# simCon.net
KiCad netlist of a schematic drawn in EAGLE
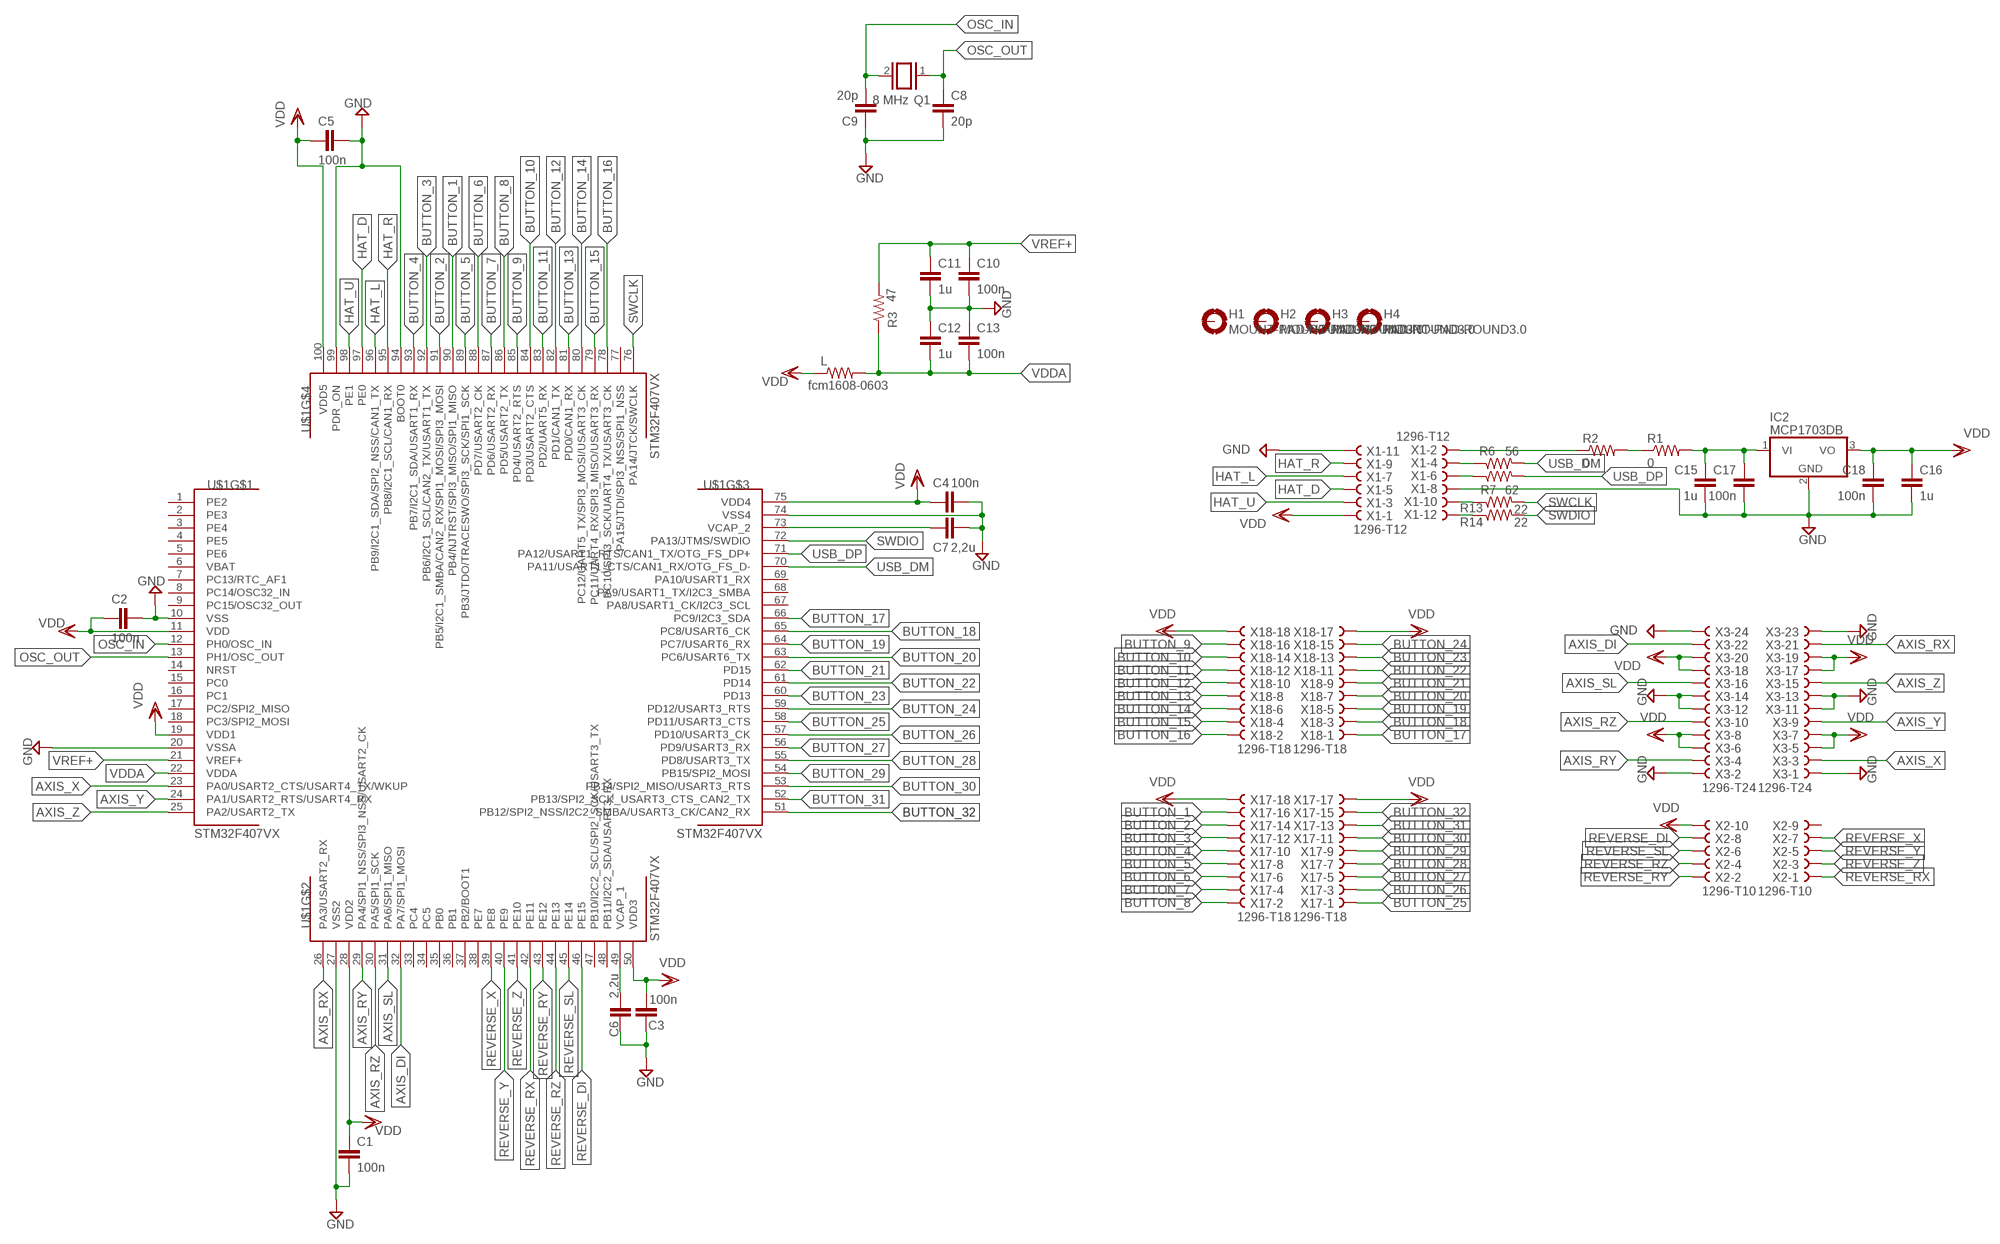
[diagram p0: schematic, sheet 1]

(export (version "E")
  (design (tool "Eeschema 10.0.6"))
  (components
    (comp (ref "C1")
      (value "100n")
      (footprint "eagle-import:C0805K")
      (libsource (lib "eagle-import") (part "C-EUC0805K"))
    )
    (comp (ref "C2")
      (value "100n")
      (footprint "eagle-import:C0805K")
      (libsource (lib "eagle-import") (part "C-EUC0805K"))
    )
    (comp (ref "C3")
      (value "100n")
      (footprint "eagle-import:C0805K")
      (libsource (lib "eagle-import") (part "C-EUC0805K"))
    )
    (comp (ref "C4")
      (value "100n")
      (footprint "eagle-import:C0805K")
      (libsource (lib "eagle-import") (part "C-EUC0805K"))
    )
    (comp (ref "C5")
      (value "100n")
      (footprint "eagle-import:C0805K")
      (libsource (lib "eagle-import") (part "C-EUC0805K"))
    )
    (comp (ref "C6")
      (value "2,2u")
      (footprint "eagle-import:C0805K")
      (libsource (lib "eagle-import") (part "C-EUC0805K"))
    )
    (comp (ref "C7")
      (value "2,2u")
      (footprint "eagle-import:C0805K")
      (libsource (lib "eagle-import") (part "C-EUC0805K"))
    )
    (comp (ref "C8")
      (value "20p")
      (footprint "eagle-import:C0805K")
      (libsource (lib "eagle-import") (part "C-EUC0805K"))
    )
    (comp (ref "C9")
      (value "20p")
      (footprint "eagle-import:C0805K")
      (libsource (lib "eagle-import") (part "C-EUC0805K"))
    )
    (comp (ref "C10")
      (value "100n")
      (footprint "eagle-import:C0805K")
      (libsource (lib "eagle-import") (part "C-EUC0805K"))
    )
    (comp (ref "C11")
      (value "1u")
      (footprint "eagle-import:C0805K")
      (libsource (lib "eagle-import") (part "C-EUC0805K"))
    )
    (comp (ref "C12")
      (value "1u")
      (footprint "eagle-import:C0805K")
      (libsource (lib "eagle-import") (part "C-EUC0805K"))
    )
    (comp (ref "C13")
      (value "100n")
      (footprint "eagle-import:C0805K")
      (libsource (lib "eagle-import") (part "C-EUC0805K"))
    )
    (comp (ref "C15")
      (value "1u")
      (footprint "eagle-import:C0805K")
      (libsource (lib "eagle-import") (part "C-EUC0805K"))
    )
    (comp (ref "C16")
      (value "1u")
      (footprint "eagle-import:C0805K")
      (libsource (lib "eagle-import") (part "C-EUC0805K"))
    )
    (comp (ref "C17")
      (value "100n")
      (footprint "eagle-import:C0805K")
      (libsource (lib "eagle-import") (part "C-EUC0805K"))
    )
    (comp (ref "C18")
      (value "100n")
      (footprint "eagle-import:C0805K")
      (libsource (lib "eagle-import") (part "C-EUC0805K"))
    )
    (comp (ref "H1")
      (value "MOUNT-PAD-ROUND3.0")
      (footprint "eagle-import:3,0-PAD")
      (libsource (lib "eagle-import") (part "MOUNT-PAD-ROUND3.0"))
    )
    (comp (ref "H2")
      (value "MOUNT-PAD-ROUND3.0")
      (footprint "eagle-import:3,0-PAD")
      (libsource (lib "eagle-import") (part "MOUNT-PAD-ROUND3.0"))
    )
    (comp (ref "H3")
      (value "MOUNT-PAD-ROUND3.0")
      (footprint "eagle-import:3,0-PAD")
      (libsource (lib "eagle-import") (part "MOUNT-PAD-ROUND3.0"))
    )
    (comp (ref "H4")
      (value "MOUNT-PAD-ROUND3.0")
      (footprint "eagle-import:3,0-PAD")
      (libsource (lib "eagle-import") (part "MOUNT-PAD-ROUND3.0"))
    )
    (comp (ref "IC2")
      (value "MCP1703DB")
      (footprint "eagle-import:SOT223")
      (libsource (lib "eagle-import") (part "MCP1703DB"))
    )
    (comp (ref "L")
      (value "fcm1608-0603")
      (footprint "eagle-import:M0805")
      (libsource (lib "eagle-import") (part "R-US_M0805"))
    )
    (comp (ref "Q1")
      (value "8 MHz")
      (footprint "eagle-import:QS")
      (libsource (lib "eagle-import") (part "XTAL/S"))
    )
    (comp (ref "R1")
      (value "0")
      (footprint "eagle-import:R1206")
      (libsource (lib "eagle-import") (part "resistor_R-US_R1206"))
    )
    (comp (ref "R2")
      (value "0")
      (footprint "eagle-import:R1206")
      (libsource (lib "eagle-import") (part "resistor_R-US_R1206"))
    )
    (comp (ref "R3")
      (value "47")
      (footprint "eagle-import:M0805")
      (libsource (lib "eagle-import") (part "R-US_M0805"))
    )
    (comp (ref "R6")
      (value "56")
      (footprint "eagle-import:M0805")
      (libsource (lib "eagle-import") (part "R-US_M0805"))
    )
    (comp (ref "R7")
      (value "62")
      (footprint "eagle-import:M0805")
      (libsource (lib "eagle-import") (part "R-US_M0805"))
    )
    (comp (ref "R13")
      (value "22")
      (footprint "eagle-import:M0805")
      (libsource (lib "eagle-import") (part "R-US_M0805"))
    )
    (comp (ref "R14")
      (value "22")
      (footprint "eagle-import:M0805")
      (libsource (lib "eagle-import") (part "R-US_M0805"))
    )
    (comp (ref "U$1")
      (value "STM32F407VX")
      (footprint "eagle-import:LQFP100")
      (libsource (lib "eagle-import") (part "STM32F407VX"))
    )
    (comp (ref "X1")
      (value "1296-T12")
      (footprint "eagle-import:1296-12")
      (libsource (lib "eagle-import") (part "1296-T12"))
    )
    (comp (ref "X2")
      (value "1296-T10")
      (footprint "eagle-import:1296-10")
      (libsource (lib "eagle-import") (part "1296-T10"))
    )
    (comp (ref "X3")
      (value "1296-T24")
      (footprint "eagle-import:1296-24")
      (libsource (lib "eagle-import") (part "1296-T24"))
    )
    (comp (ref "X17")
      (value "1296-T18")
      (footprint "eagle-import:1296-18")
      (libsource (lib "eagle-import") (part "1296-T18"))
    )
    (comp (ref "X18")
      (value "1296-T18")
      (footprint "eagle-import:1296-18")
      (libsource (lib "eagle-import") (part "1296-T18"))
    )
  )
  (nets
    (net (code "1") (name "AXIS_DI") (class "Default")
      (node (ref "U$1") (pin "32") (pinfunction "PA7/SPI1_MOSI_32") (pintype "bidirectional"))
      (node (ref "X3") (pin "22") (pinfunction "B_22") (pintype "passive"))
    )
    (net (code "2") (name "AXIS_RX") (class "Default")
      (node (ref "U$1") (pin "26") (pinfunction "PA3/USART2_RX_26") (pintype "bidirectional"))
      (node (ref "X3") (pin "21") (pinfunction "B_21") (pintype "passive"))
    )
    (net (code "3") (name "AXIS_RY") (class "Default")
      (node (ref "U$1") (pin "29") (pinfunction "PA4/SPI1_NSS/SPI3_NSS/USART2_CK_29") (pintype "bidirectional"))
      (node (ref "X3") (pin "4") (pinfunction "B_4") (pintype "passive"))
    )
    (net (code "4") (name "AXIS_RZ") (class "Default")
      (node (ref "U$1") (pin "30") (pinfunction "PA5/SPI1_SCK_30") (pintype "bidirectional"))
      (node (ref "X3") (pin "10") (pinfunction "B_10") (pintype "passive"))
    )
    (net (code "5") (name "AXIS_SL") (class "Default")
      (node (ref "U$1") (pin "31") (pinfunction "PA6/SPI1_MISO_31") (pintype "bidirectional"))
      (node (ref "X3") (pin "16") (pinfunction "B_16") (pintype "passive"))
    )
    (net (code "6") (name "AXIS_X") (class "Default")
      (node (ref "U$1") (pin "23") (pinfunction "PA0/USART2_CTS/USART4_TX/WKUP_23") (pintype "bidirectional"))
      (node (ref "X3") (pin "3") (pinfunction "B_3") (pintype "passive"))
    )
    (net (code "7") (name "AXIS_Y") (class "Default")
      (node (ref "U$1") (pin "24") (pinfunction "PA1/USART2_RTS/USART4_RX_24") (pintype "bidirectional"))
      (node (ref "X3") (pin "9") (pinfunction "B_9") (pintype "passive"))
    )
    (net (code "8") (name "AXIS_Z") (class "Default")
      (node (ref "U$1") (pin "25") (pinfunction "PA2/USART2_TX_25") (pintype "bidirectional"))
      (node (ref "X3") (pin "15") (pinfunction "B_15") (pintype "passive"))
    )
    (net (code "9") (name "BUTTON_1") (class "Default")
      (node (ref "U$1") (pin "90") (pinfunction "PB4/NJTRST/SPI3_MISO/SPI1_MISO_90") (pintype "bidirectional"))
      (node (ref "X17") (pin "16") (pinfunction "B_16") (pintype "passive"))
    )
    (net (code "10") (name "BUTTON_2") (class "Default")
      (node (ref "U$1") (pin "91") (pinfunction "PB5/I2C1_SMBA/CAN2_RX/SPI1_MOSI/SPI3_MOSI_91") (pintype "bidirectional"))
      (node (ref "X17") (pin "14") (pinfunction "B_14") (pintype "passive"))
    )
    (net (code "11") (name "BUTTON_3") (class "Default")
      (node (ref "U$1") (pin "92") (pinfunction "PB6/I2C1_SCL/CAN2_TX/USART1_TX_92") (pintype "bidirectional"))
      (node (ref "X17") (pin "12") (pinfunction "B_12") (pintype "passive"))
    )
    (net (code "12") (name "BUTTON_4") (class "Default")
      (node (ref "U$1") (pin "93") (pinfunction "PB7/I2C1_SDA/USART1_RX_93") (pintype "bidirectional"))
      (node (ref "X17") (pin "10") (pinfunction "B_10") (pintype "passive"))
    )
    (net (code "13") (name "BUTTON_5") (class "Default")
      (node (ref "U$1") (pin "89") (pinfunction "PB3/JTDO/TRACESWO/SPI3_SCK/SPI1_SCK_89") (pintype "bidirectional"))
      (node (ref "X17") (pin "8") (pinfunction "B_8") (pintype "passive"))
    )
    (net (code "14") (name "BUTTON_6") (class "Default")
      (node (ref "U$1") (pin "88") (pinfunction "PD7/USART2_CK_88") (pintype "bidirectional"))
      (node (ref "X17") (pin "6") (pinfunction "B_6") (pintype "passive"))
    )
    (net (code "15") (name "BUTTON_7") (class "Default")
      (node (ref "U$1") (pin "87") (pinfunction "PD6/USART2_RX_87") (pintype "bidirectional"))
      (node (ref "X17") (pin "4") (pinfunction "B_4") (pintype "passive"))
    )
    (net (code "16") (name "BUTTON_8") (class "Default")
      (node (ref "U$1") (pin "86") (pinfunction "PD5/USART2_TX_86") (pintype "bidirectional"))
      (node (ref "X17") (pin "2") (pinfunction "B_2") (pintype "passive"))
    )
    (net (code "17") (name "BUTTON_9") (class "Default")
      (node (ref "U$1") (pin "85") (pinfunction "PD4/USART2_RTS_85") (pintype "bidirectional"))
      (node (ref "X18") (pin "16") (pinfunction "B_16") (pintype "passive"))
    )
    (net (code "18") (name "BUTTON_10") (class "Default")
      (node (ref "U$1") (pin "84") (pinfunction "PD3/USART2_CTS_84") (pintype "bidirectional"))
      (node (ref "X18") (pin "14") (pinfunction "B_14") (pintype "passive"))
    )
    (net (code "19") (name "BUTTON_11") (class "Default")
      (node (ref "U$1") (pin "83") (pinfunction "PD2/UART5_RX_83") (pintype "bidirectional"))
      (node (ref "X18") (pin "12") (pinfunction "B_12") (pintype "passive"))
    )
    (net (code "20") (name "BUTTON_12") (class "Default")
      (node (ref "U$1") (pin "82") (pinfunction "PD1/CAN1_TX_82") (pintype "bidirectional"))
      (node (ref "X18") (pin "10") (pinfunction "B_10") (pintype "passive"))
    )
    (net (code "21") (name "BUTTON_13") (class "Default")
      (node (ref "U$1") (pin "81") (pinfunction "PD0/CAN1_RX_81") (pintype "bidirectional"))
      (node (ref "X18") (pin "8") (pinfunction "B_8") (pintype "passive"))
    )
    (net (code "22") (name "BUTTON_14") (class "Default")
      (node (ref "U$1") (pin "80") (pinfunction "PC12/UART5_TX/SPI3_MOSI/USART3_CK_80") (pintype "bidirectional"))
      (node (ref "X18") (pin "6") (pinfunction "B_6") (pintype "passive"))
    )
    (net (code "23") (name "BUTTON_15") (class "Default")
      (node (ref "U$1") (pin "79") (pinfunction "PC11/UART4_RX/SPI3_MISO/USART3_RX_79") (pintype "bidirectional"))
      (node (ref "X18") (pin "4") (pinfunction "B_4") (pintype "passive"))
    )
    (net (code "24") (name "BUTTON_16") (class "Default")
      (node (ref "U$1") (pin "78") (pinfunction "PC10/SPI3_SCK/UART4_TX/USART3_CK_78") (pintype "bidirectional"))
      (node (ref "X18") (pin "2") (pinfunction "B_2") (pintype "passive"))
    )
    (net (code "25") (name "BUTTON_17") (class "Default")
      (node (ref "U$1") (pin "66") (pinfunction "PC9/I2C3_SDA_66") (pintype "bidirectional"))
      (node (ref "X18") (pin "1") (pinfunction "B_1") (pintype "passive"))
    )
    (net (code "26") (name "BUTTON_18") (class "Default")
      (node (ref "U$1") (pin "65") (pinfunction "PC8/USART6_CK_65") (pintype "bidirectional"))
      (node (ref "X18") (pin "3") (pinfunction "B_3") (pintype "passive"))
    )
    (net (code "27") (name "BUTTON_19") (class "Default")
      (node (ref "U$1") (pin "64") (pinfunction "PC7/USART6_RX_64") (pintype "bidirectional"))
      (node (ref "X18") (pin "5") (pinfunction "B_5") (pintype "passive"))
    )
    (net (code "28") (name "BUTTON_20") (class "Default")
      (node (ref "U$1") (pin "63") (pinfunction "PC6/USART6_TX_63") (pintype "bidirectional"))
      (node (ref "X18") (pin "7") (pinfunction "B_7") (pintype "passive"))
    )
    (net (code "29") (name "BUTTON_21") (class "Default")
      (node (ref "U$1") (pin "62") (pinfunction "PD15_62") (pintype "bidirectional"))
      (node (ref "X18") (pin "9") (pinfunction "B_9") (pintype "passive"))
    )
    (net (code "30") (name "BUTTON_22") (class "Default")
      (node (ref "U$1") (pin "61") (pinfunction "PD14_61") (pintype "bidirectional"))
      (node (ref "X18") (pin "11") (pinfunction "B_11") (pintype "passive"))
    )
    (net (code "31") (name "BUTTON_23") (class "Default")
      (node (ref "U$1") (pin "60") (pinfunction "PD13_60") (pintype "bidirectional"))
      (node (ref "X18") (pin "13") (pinfunction "B_13") (pintype "passive"))
    )
    (net (code "32") (name "BUTTON_24") (class "Default")
      (node (ref "U$1") (pin "59") (pinfunction "PD12/USART3_RTS_59") (pintype "bidirectional"))
      (node (ref "X18") (pin "15") (pinfunction "B_15") (pintype "passive"))
    )
    (net (code "33") (name "BUTTON_25") (class "Default")
      (node (ref "U$1") (pin "58") (pinfunction "PD11/USART3_CTS_58") (pintype "bidirectional"))
      (node (ref "X17") (pin "1") (pinfunction "B_1") (pintype "passive"))
    )
    (net (code "34") (name "BUTTON_26") (class "Default")
      (node (ref "U$1") (pin "57") (pinfunction "PD10/USART3_CK_57") (pintype "bidirectional"))
      (node (ref "X17") (pin "3") (pinfunction "B_3") (pintype "passive"))
    )
    (net (code "35") (name "BUTTON_27") (class "Default")
      (node (ref "U$1") (pin "56") (pinfunction "PD9/USART3_RX_56") (pintype "bidirectional"))
      (node (ref "X17") (pin "5") (pinfunction "B_5") (pintype "passive"))
    )
    (net (code "36") (name "BUTTON_28") (class "Default")
      (node (ref "U$1") (pin "55") (pinfunction "PD8/USART3_TX_55") (pintype "bidirectional"))
      (node (ref "X17") (pin "7") (pinfunction "B_7") (pintype "passive"))
    )
    (net (code "37") (name "BUTTON_29") (class "Default")
      (node (ref "U$1") (pin "54") (pinfunction "PB15/SPI2_MOSI_54") (pintype "bidirectional"))
      (node (ref "X17") (pin "9") (pinfunction "B_9") (pintype "passive"))
    )
    (net (code "38") (name "BUTTON_30") (class "Default")
      (node (ref "U$1") (pin "53") (pinfunction "PB14/SPI2_MISO/USART3_RTS_53") (pintype "bidirectional"))
      (node (ref "X17") (pin "11") (pinfunction "B_11") (pintype "passive"))
    )
    (net (code "39") (name "BUTTON_31") (class "Default")
      (node (ref "U$1") (pin "52") (pinfunction "PB13/SPI2_SCK_USART3_CTS_CAN2_TX_52") (pintype "bidirectional"))
      (node (ref "X17") (pin "13") (pinfunction "B_13") (pintype "passive"))
    )
    (net (code "40") (name "BUTTON_32") (class "Default")
      (node (ref "U$1") (pin "51") (pinfunction "PB12/SPI2_NSS/I2C2_SMBA/USART3_CK/CAN2_RX_51") (pintype "bidirectional"))
      (node (ref "X17") (pin "15") (pinfunction "B_15") (pintype "passive"))
    )
    (net (code "41") (name "GND") (class "Default")
      (node (ref "C1") (pin "2") (pinfunction "2_2") (pintype "passive"))
      (node (ref "C10") (pin "2") (pinfunction "2_2") (pintype "passive"))
      (node (ref "C11") (pin "2") (pinfunction "2_2") (pintype "passive"))
      (node (ref "C12") (pin "1") (pinfunction "1_1") (pintype "passive"))
      (node (ref "C13") (pin "1") (pinfunction "1_1") (pintype "passive"))
      (node (ref "C15") (pin "2") (pinfunction "2_2") (pintype "passive"))
      (node (ref "C16") (pin "2") (pinfunction "2_2") (pintype "passive"))
      (node (ref "C17") (pin "2") (pinfunction "2_2") (pintype "passive"))
      (node (ref "C18") (pin "2") (pinfunction "2_2") (pintype "passive"))
      (node (ref "C2") (pin "1") (pinfunction "1_1") (pintype "passive"))
      (node (ref "C3") (pin "1") (pinfunction "1_1") (pintype "passive"))
      (node (ref "C4") (pin "1") (pinfunction "1_1") (pintype "passive"))
      (node (ref "C5") (pin "1") (pinfunction "1_1") (pintype "passive"))
      (node (ref "C6") (pin "1") (pinfunction "1_1") (pintype "passive"))
      (node (ref "C7") (pin "1") (pinfunction "1_1") (pintype "passive"))
      (node (ref "C8") (pin "2") (pinfunction "2_2") (pintype "passive"))
      (node (ref "C9") (pin "1") (pinfunction "1_1") (pintype "passive"))
      (node (ref "IC2") (pin "2") (pinfunction "GND_2") (pintype "passive"))
      (node (ref "U$1") (pin "10") (pinfunction "VSS_10") (pintype "bidirectional"))
      (node (ref "U$1") (pin "20") (pinfunction "VSSA_20") (pintype "bidirectional"))
      (node (ref "U$1") (pin "27") (pinfunction "VSS2_27") (pintype "bidirectional"))
      (node (ref "U$1") (pin "74") (pinfunction "VSS4_74") (pintype "bidirectional"))
      (node (ref "U$1") (pin "94") (pinfunction "BOOT0_94") (pintype "bidirectional"))
      (node (ref "U$1") (pin "99") (pinfunction "PDR_ON_99") (pintype "bidirectional"))
      (node (ref "X1") (pin "11") (pinfunction "B_11") (pintype "passive"))
      (node (ref "X1") (pin "8") (pinfunction "B_8") (pintype "passive"))
      (node (ref "X3") (pin "1") (pinfunction "B_1") (pintype "passive"))
      (node (ref "X3") (pin "11") (pinfunction "B_11") (pintype "passive"))
      (node (ref "X3") (pin "12") (pinfunction "B_12") (pintype "passive"))
      (node (ref "X3") (pin "13") (pinfunction "B_13") (pintype "passive"))
      (node (ref "X3") (pin "14") (pinfunction "B_14") (pintype "passive"))
      (node (ref "X3") (pin "2") (pinfunction "B_2") (pintype "passive"))
      (node (ref "X3") (pin "23") (pinfunction "B_23") (pintype "passive"))
      (node (ref "X3") (pin "24") (pinfunction "B_24") (pintype "passive"))
    )
    (net (code "42") (name "HAT_D") (class "Default")
      (node (ref "U$1") (pin "97") (pinfunction "PE0_97") (pintype "bidirectional"))
      (node (ref "X1") (pin "5") (pinfunction "B_5") (pintype "passive"))
    )
    (net (code "43") (name "HAT_L") (class "Default")
      (node (ref "U$1") (pin "96") (pinfunction "PB9/I2C1_SDA/SPI2_NSS/CAN1_TX_96") (pintype "bidirectional"))
      (node (ref "X1") (pin "7") (pinfunction "B_7") (pintype "passive"))
    )
    (net (code "44") (name "HAT_R") (class "Default")
      (node (ref "U$1") (pin "95") (pinfunction "PB8/I2C1_SCL/CAN1_RX_95") (pintype "bidirectional"))
      (node (ref "X1") (pin "9") (pinfunction "B_9") (pintype "passive"))
    )
    (net (code "45") (name "HAT_U") (class "Default")
      (node (ref "U$1") (pin "98") (pinfunction "PE1_98") (pintype "bidirectional"))
      (node (ref "X1") (pin "3") (pinfunction "B_3") (pintype "passive"))
    )
    (net (code "46") (name "Net-(IC2-VI)") (class "Default")
      (node (ref "C15") (pin "1") (pinfunction "1_1") (pintype "passive"))
      (node (ref "C17") (pin "1") (pinfunction "1_1") (pintype "passive"))
      (node (ref "IC2") (pin "1") (pinfunction "VI_1") (pintype "input"))
      (node (ref "R1") (pin "2") (pinfunction "2_2") (pintype "passive"))
    )
    (net (code "47") (name "Net-(R1-Pad1)") (class "Default")
      (node (ref "R1") (pin "1") (pinfunction "1_1") (pintype "passive"))
      (node (ref "R2") (pin "2") (pinfunction "2_2") (pintype "passive"))
    )
    (net (code "48") (name "Net-(U$1B-VCAP_1)") (class "Default")
      (node (ref "C6") (pin "2") (pinfunction "2_2") (pintype "passive"))
      (node (ref "U$1") (pin "49") (pinfunction "VCAP_1_49") (pintype "bidirectional"))
    )
    (net (code "49") (name "Net-(U$1C-VCAP_2)") (class "Default")
      (node (ref "C7") (pin "2") (pinfunction "2_2") (pintype "passive"))
      (node (ref "U$1") (pin "73") (pinfunction "VCAP_2_73") (pintype "bidirectional"))
    )
    (net (code "50") (name "Net-(X1B-B)") (class "Default")
      (node (ref "R13") (pin "1") (pinfunction "1_1") (pintype "passive"))
      (node (ref "X1") (pin "10") (pinfunction "B_10") (pintype "passive"))
    )
    (net (code "51") (name "Net-(X1D-B)") (class "Default")
      (node (ref "R14") (pin "1") (pinfunction "1_1") (pintype "passive"))
      (node (ref "X1") (pin "12") (pinfunction "B_12") (pintype "passive"))
    )
    (net (code "52") (name "Net-(X1E-B)") (class "Default")
      (node (ref "R2") (pin "1") (pinfunction "1_1") (pintype "passive"))
      (node (ref "X1") (pin "2") (pinfunction "B_2") (pintype "passive"))
    )
    (net (code "53") (name "Net-(X1G-B)") (class "Default")
      (node (ref "R6") (pin "1") (pinfunction "1_1") (pintype "passive"))
      (node (ref "X1") (pin "4") (pinfunction "B_4") (pintype "passive"))
    )
    (net (code "54") (name "Net-(X1I-B)") (class "Default")
      (node (ref "R7") (pin "1") (pinfunction "1_1") (pintype "passive"))
      (node (ref "X1") (pin "6") (pinfunction "B_6") (pintype "passive"))
    )
    (net (code "55") (name "OSC_IN") (class "Default")
      (node (ref "C9") (pin "2") (pinfunction "2_2") (pintype "passive"))
      (node (ref "Q1") (pin "2") (pinfunction "2_2") (pintype "passive"))
      (node (ref "U$1") (pin "12") (pinfunction "PH0/OSC_IN_12") (pintype "bidirectional"))
    )
    (net (code "56") (name "OSC_OUT") (class "Default")
      (node (ref "C8") (pin "1") (pinfunction "1_1") (pintype "passive"))
      (node (ref "Q1") (pin "1") (pinfunction "1_1") (pintype "passive"))
      (node (ref "U$1") (pin "13") (pinfunction "PH1/OSC_OUT_13") (pintype "bidirectional"))
    )
    (net (code "57") (name "REVERSE_DI") (class "Default")
      (node (ref "U$1") (pin "46") (pinfunction "PE15_46") (pintype "bidirectional"))
      (node (ref "X2") (pin "8") (pinfunction "B_8") (pintype "passive"))
    )
    (net (code "58") (name "REVERSE_RX") (class "Default")
      (node (ref "U$1") (pin "42") (pinfunction "PE11_42") (pintype "bidirectional"))
      (node (ref "X2") (pin "1") (pinfunction "B_1") (pintype "passive"))
    )
    (net (code "59") (name "REVERSE_RY") (class "Default")
      (node (ref "U$1") (pin "43") (pinfunction "PE12_43") (pintype "bidirectional"))
      (node (ref "X2") (pin "2") (pinfunction "B_2") (pintype "passive"))
    )
    (net (code "60") (name "REVERSE_RZ") (class "Default")
      (node (ref "U$1") (pin "44") (pinfunction "PE13_44") (pintype "bidirectional"))
      (node (ref "X2") (pin "4") (pinfunction "B_4") (pintype "passive"))
    )
    (net (code "61") (name "REVERSE_SL") (class "Default")
      (node (ref "U$1") (pin "45") (pinfunction "PE14_45") (pintype "bidirectional"))
      (node (ref "X2") (pin "6") (pinfunction "B_6") (pintype "passive"))
    )
    (net (code "62") (name "REVERSE_X") (class "Default")
      (node (ref "U$1") (pin "39") (pinfunction "PE8_39") (pintype "bidirectional"))
      (node (ref "X2") (pin "7") (pinfunction "B_7") (pintype "passive"))
    )
    (net (code "63") (name "REVERSE_Y") (class "Default")
      (node (ref "U$1") (pin "40") (pinfunction "PE9_40") (pintype "bidirectional"))
      (node (ref "X2") (pin "5") (pinfunction "B_5") (pintype "passive"))
    )
    (net (code "64") (name "REVERSE_Z") (class "Default")
      (node (ref "U$1") (pin "41") (pinfunction "PE10_41") (pintype "bidirectional"))
      (node (ref "X2") (pin "3") (pinfunction "B_3") (pintype "passive"))
    )
    (net (code "65") (name "SWCLK") (class "Default")
      (node (ref "R13") (pin "2") (pinfunction "2_2") (pintype "passive"))
      (node (ref "U$1") (pin "76") (pinfunction "PA14/JTCK/SWCLK_76") (pintype "bidirectional"))
    )
    (net (code "66") (name "SWDIO") (class "Default")
      (node (ref "R14") (pin "2") (pinfunction "2_2") (pintype "passive"))
      (node (ref "U$1") (pin "72") (pinfunction "PA13/JTMS/SWDIO_72") (pintype "bidirectional"))
    )
    (net (code "67") (name "USB_DM") (class "Default")
      (node (ref "R6") (pin "2") (pinfunction "2_2") (pintype "passive"))
      (node (ref "U$1") (pin "70") (pinfunction "PA11/USART1_CTS/CAN1_RX/OTG_FS_D-_70") (pintype "bidirectional"))
    )
    (net (code "68") (name "USB_DP") (class "Default")
      (node (ref "R7") (pin "2") (pinfunction "2_2") (pintype "passive"))
      (node (ref "U$1") (pin "71") (pinfunction "PA12/USART1_RTS/CAN1_TX/OTG_FS_DP+_71") (pintype "bidirectional"))
    )
    (net (code "69") (name "VDD") (class "Default")
      (node (ref "C1") (pin "1") (pinfunction "1_1") (pintype "passive"))
      (node (ref "C16") (pin "1") (pinfunction "1_1") (pintype "passive"))
      (node (ref "C18") (pin "1") (pinfunction "1_1") (pintype "passive"))
      (node (ref "C2") (pin "2") (pinfunction "2_2") (pintype "passive"))
      (node (ref "C3") (pin "2") (pinfunction "2_2") (pintype "passive"))
      (node (ref "C4") (pin "2") (pinfunction "2_2") (pintype "passive"))
      (node (ref "C5") (pin "2") (pinfunction "2_2") (pintype "passive"))
      (node (ref "IC2") (pin "3") (pinfunction "VO_3") (pintype "passive"))
      (node (ref "L") (pin "1") (pinfunction "1_1") (pintype "passive"))
      (node (ref "U$1") (pin "100") (pinfunction "VDD5_100") (pintype "bidirectional"))
      (node (ref "U$1") (pin "11") (pinfunction "VDD_11") (pintype "bidirectional"))
      (node (ref "U$1") (pin "19") (pinfunction "VDD1_19") (pintype "bidirectional"))
      (node (ref "U$1") (pin "28") (pinfunction "VDD2_28") (pintype "bidirectional"))
      (node (ref "U$1") (pin "50") (pinfunction "VDD3_50") (pintype "bidirectional"))
      (node (ref "U$1") (pin "75") (pinfunction "VDD4_75") (pintype "bidirectional"))
      (node (ref "X1") (pin "1") (pinfunction "B_1") (pintype "passive"))
      (node (ref "X17") (pin "17") (pinfunction "B_17") (pintype "passive"))
      (node (ref "X17") (pin "18") (pinfunction "B_18") (pintype "passive"))
      (node (ref "X18") (pin "17") (pinfunction "B_17") (pintype "passive"))
      (node (ref "X18") (pin "18") (pinfunction "B_18") (pintype "passive"))
      (node (ref "X2") (pin "10") (pinfunction "B_10") (pintype "passive"))
      (node (ref "X3") (pin "17") (pinfunction "B_17") (pintype "passive"))
      (node (ref "X3") (pin "18") (pinfunction "B_18") (pintype "passive"))
      (node (ref "X3") (pin "19") (pinfunction "B_19") (pintype "passive"))
      (node (ref "X3") (pin "20") (pinfunction "B_20") (pintype "passive"))
      (node (ref "X3") (pin "5") (pinfunction "B_5") (pintype "passive"))
      (node (ref "X3") (pin "6") (pinfunction "B_6") (pintype "passive"))
      (node (ref "X3") (pin "7") (pinfunction "B_7") (pintype "passive"))
      (node (ref "X3") (pin "8") (pinfunction "B_8") (pintype "passive"))
    )
    (net (code "70") (name "VDDA") (class "Default")
      (node (ref "C12") (pin "2") (pinfunction "2_2") (pintype "passive"))
      (node (ref "C13") (pin "2") (pinfunction "2_2") (pintype "passive"))
      (node (ref "L") (pin "2") (pinfunction "2_2") (pintype "passive"))
      (node (ref "R3") (pin "1") (pinfunction "1_1") (pintype "passive"))
      (node (ref "U$1") (pin "22") (pinfunction "VDDA_22") (pintype "bidirectional"))
    )
    (net (code "71") (name "VREF+") (class "Default")
      (node (ref "C10") (pin "1") (pinfunction "1_1") (pintype "passive"))
      (node (ref "C11") (pin "1") (pinfunction "1_1") (pintype "passive"))
      (node (ref "R3") (pin "2") (pinfunction "2_2") (pintype "passive"))
      (node (ref "U$1") (pin "21") (pinfunction "VREF+_21") (pintype "bidirectional"))
    )
    (net (code "72") (name "unconnected-(H1-MOUNT-PadB3,0)") (class "Default")
      (node (ref "H1") (pin "B3,0") (pinfunction "MOUNT_B3,0") (pintype "passive"))
    )
    (net (code "73") (name "unconnected-(H2-MOUNT-PadB3,0)") (class "Default")
      (node (ref "H2") (pin "B3,0") (pinfunction "MOUNT_B3,0") (pintype "passive"))
    )
    (net (code "74") (name "unconnected-(H3-MOUNT-PadB3,0)") (class "Default")
      (node (ref "H3") (pin "B3,0") (pinfunction "MOUNT_B3,0") (pintype "passive"))
    )
    (net (code "75") (name "unconnected-(H4-MOUNT-PadB3,0)") (class "Default")
      (node (ref "H4") (pin "B3,0") (pinfunction "MOUNT_B3,0") (pintype "passive"))
    )
    (net (code "76") (name "unconnected-(U$1A-NRST-Pad14)") (class "Default")
      (node (ref "U$1") (pin "14") (pinfunction "NRST_14") (pintype "bidirectional"))
    )
    (net (code "77") (name "unconnected-(U$1A-PC0-Pad15)") (class "Default")
      (node (ref "U$1") (pin "15") (pinfunction "PC0_15") (pintype "bidirectional"))
    )
    (net (code "78") (name "unconnected-(U$1A-PC1-Pad16)") (class "Default")
      (node (ref "U$1") (pin "16") (pinfunction "PC1_16") (pintype "bidirectional"))
    )
    (net (code "79") (name "unconnected-(U$1A-PC2{slash}SPI2_MISO-Pad17)") (class "Default")
      (node (ref "U$1") (pin "17") (pinfunction "PC2/SPI2_MISO_17") (pintype "bidirectional"))
    )
    (net (code "80") (name "unconnected-(U$1A-PC3{slash}SPI2_MOSI-Pad18)") (class "Default")
      (node (ref "U$1") (pin "18") (pinfunction "PC3/SPI2_MOSI_18") (pintype "bidirectional"))
    )
    (net (code "81") (name "unconnected-(U$1A-PC13{slash}RTC_AF1-Pad7)") (class "Default")
      (node (ref "U$1") (pin "7") (pinfunction "PC13/RTC_AF1_7") (pintype "bidirectional"))
    )
    (net (code "82") (name "unconnected-(U$1A-PC14{slash}OSC32_IN-Pad8)") (class "Default")
      (node (ref "U$1") (pin "8") (pinfunction "PC14/OSC32_IN_8") (pintype "bidirectional"))
    )
    (net (code "83") (name "unconnected-(U$1A-PC15{slash}OSC32_OUT-Pad9)") (class "Default")
      (node (ref "U$1") (pin "9") (pinfunction "PC15/OSC32_OUT_9") (pintype "bidirectional"))
    )
    (net (code "84") (name "unconnected-(U$1A-PE2-Pad1)") (class "Default")
      (node (ref "U$1") (pin "1") (pinfunction "PE2_1") (pintype "bidirectional"))
    )
    (net (code "85") (name "unconnected-(U$1A-PE3-Pad2)") (class "Default")
      (node (ref "U$1") (pin "2") (pinfunction "PE3_2") (pintype "bidirectional"))
    )
    (net (code "86") (name "unconnected-(U$1A-PE4-Pad3)") (class "Default")
      (node (ref "U$1") (pin "3") (pinfunction "PE4_3") (pintype "bidirectional"))
    )
    (net (code "87") (name "unconnected-(U$1A-PE5-Pad4)") (class "Default")
      (node (ref "U$1") (pin "4") (pinfunction "PE5_4") (pintype "bidirectional"))
    )
    (net (code "88") (name "unconnected-(U$1A-PE6-Pad5)") (class "Default")
      (node (ref "U$1") (pin "5") (pinfunction "PE6_5") (pintype "bidirectional"))
    )
    (net (code "89") (name "unconnected-(U$1A-VBAT-Pad6)") (class "Default")
      (node (ref "U$1") (pin "6") (pinfunction "VBAT_6") (pintype "bidirectional"))
    )
    (net (code "90") (name "unconnected-(U$1B-PB0-Pad35)") (class "Default")
      (node (ref "U$1") (pin "35") (pinfunction "PB0_35") (pintype "bidirectional"))
    )
    (net (code "91") (name "unconnected-(U$1B-PB1-Pad36)") (class "Default")
      (node (ref "U$1") (pin "36") (pinfunction "PB1_36") (pintype "bidirectional"))
    )
    (net (code "92") (name "unconnected-(U$1B-PB2{slash}BOOT1-Pad37)") (class "Default")
      (node (ref "U$1") (pin "37") (pinfunction "PB2/BOOT1_37") (pintype "bidirectional"))
    )
    (net (code "93") (name "unconnected-(U$1B-PB10{slash}I2C2_SCL{slash}SPI2_SCK{slash}USART3_TX-Pad47)") (class "Default")
      (node (ref "U$1") (pin "47") (pinfunction "PB10/I2C2_SCL/SPI2_SCK/USART3_TX_47") (pintype "bidirectional"))
    )
    (net (code "94") (name "unconnected-(U$1B-PB11{slash}I2C2_SDA{slash}USART3_RX-Pad48)") (class "Default")
      (node (ref "U$1") (pin "48") (pinfunction "PB11/I2C2_SDA/USART3_RX_48") (pintype "bidirectional"))
    )
    (net (code "95") (name "unconnected-(U$1B-PC4-Pad33)") (class "Default")
      (node (ref "U$1") (pin "33") (pinfunction "PC4_33") (pintype "bidirectional"))
    )
    (net (code "96") (name "unconnected-(U$1B-PC5-Pad34)") (class "Default")
      (node (ref "U$1") (pin "34") (pinfunction "PC5_34") (pintype "bidirectional"))
    )
    (net (code "97") (name "unconnected-(U$1B-PE7-Pad38)") (class "Default")
      (node (ref "U$1") (pin "38") (pinfunction "PE7_38") (pintype "bidirectional"))
    )
    (net (code "98") (name "unconnected-(U$1C-PA8{slash}USART1_CK{slash}I2C3_SCL-Pad67)") (class "Default")
      (node (ref "U$1") (pin "67") (pinfunction "PA8/USART1_CK/I2C3_SCL_67") (pintype "bidirectional"))
    )
    (net (code "99") (name "unconnected-(U$1C-PA9{slash}USART1_TX{slash}I2C3_SMBA-Pad68)") (class "Default")
      (node (ref "U$1") (pin "68") (pinfunction "PA9/USART1_TX/I2C3_SMBA_68") (pintype "bidirectional"))
    )
    (net (code "100") (name "unconnected-(U$1C-PA10{slash}USART1_RX-Pad69)") (class "Default")
      (node (ref "U$1") (pin "69") (pinfunction "PA10/USART1_RX_69") (pintype "bidirectional"))
    )
    (net (code "101") (name "unconnected-(U$1D-PA15{slash}JTDI{slash}SPI3_NSS{slash}SPI1_NSS-Pad77)") (class "Default")
      (node (ref "U$1") (pin "77") (pinfunction "PA15/JTDI/SPI3_NSS/SPI1_NSS_77") (pintype "bidirectional"))
    )
    (net (code "102") (name "unconnected-(X2J-B-Pad9)") (class "Default")
      (node (ref "X2") (pin "9") (pinfunction "B_9") (pintype "passive"))
    )
  )
)
